# Preamp_schematic.net
KiCad netlist of a schematic drawn in Altium Designer
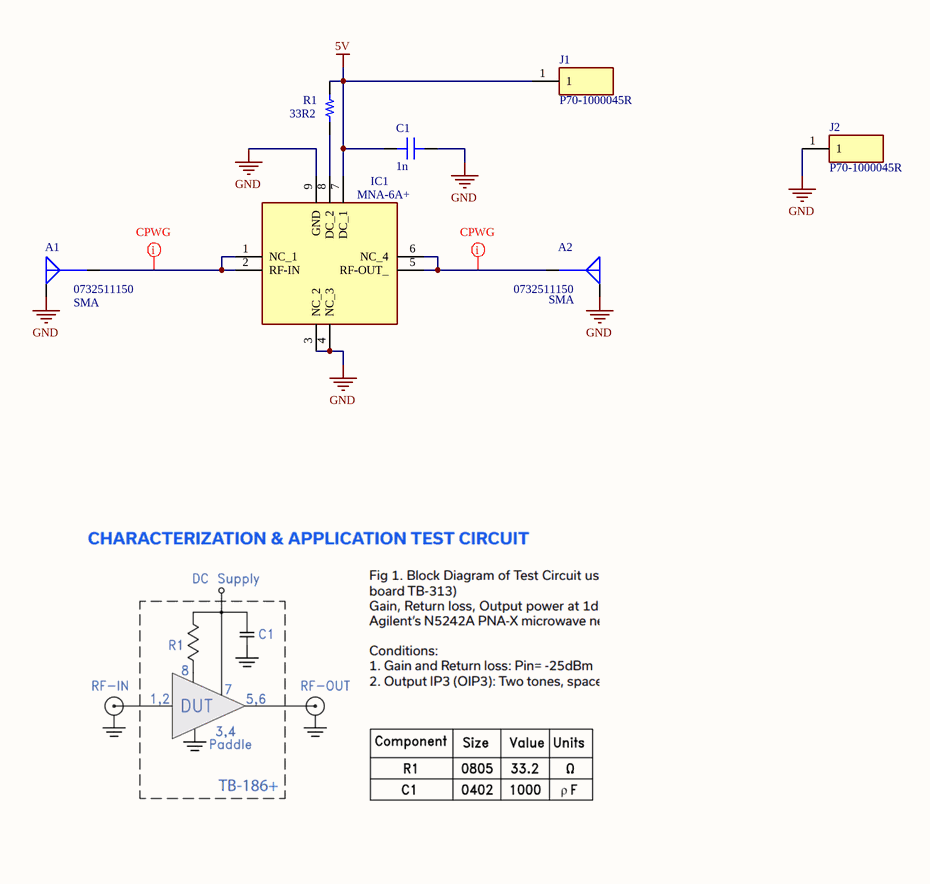
[diagram p0: Preamp_schematic.SchDoc]

(export (version "E")
  (design (tool "Eeschema 10.0.6"))
  (components
    (comp (ref "A1")
      (value "0732511150")
      (footprint "MOLEX SD-73251-115")
      (description "CONN SMA RCPT STR 50OHM EDGE MNT")
      (fields (field (name "CONNECTOR STYLE") "SMA") (field (name "MANUFACTURER") "Molex"))
      (libsource (lib "Celestial Altium Library - altium_library") (part "Basic Antenna"))
    )
    (comp (ref "A2")
      (value "0732511150")
      (footprint "MOLEX SD-73251-115")
      (description "CONN SMA RCPT STR 50OHM EDGE MNT")
      (fields (field (name "CONNECTOR STYLE") "SMA") (field (name "MANUFACTURER") "Molex"))
      (libsource (lib "Celestial Altium Library - altium_library") (part "Basic Antenna"))
    )
    (comp (ref "C1")
      (value "1n")
      (footprint "CAP 0603_1608 RF")
      (description "CAP CER 1000PF 50V 0603")
      (fields (field (name "PART NUMBER") "UMK107SD102JA-T") (field (name "MANUFACTURER") "Taiyo Yuden"))
      (libsource (lib "Celestial Altium Library - altium_library") (part "Capacitor"))
    )
    (comp (ref "IC1")
      (value "MNA-6A+")
      (footprint "SamacSys:MNA6A")
      (description "Integrated Circuit")
      (fields (field (name "MOUSER PART NUMBER") "139-MNA-6A"))
      (libsource (lib "*") (part "MNA-6A+"))
    )
    (comp (ref "J1")
      (value "P70-1000045R")
      (footprint "SamacSys:P701000045R")
      (description "Connector")
      (fields (field (name "MOUSER PART NUMBER") "855-P70-1000045R"))
      (libsource (lib "*") (part "P70-1000045R"))
    )
    (comp (ref "J2")
      (value "P70-1000045R")
      (footprint "SamacSys:P701000045R")
      (description "Connector")
      (fields (field (name "MOUSER PART NUMBER") "855-P70-1000045R"))
      (libsource (lib "*") (part "P70-1000045R"))
    )
    (comp (ref "R1")
      (value "33R2")
      (footprint "RES 0805_2012")
      (description "RES SMD 33.2 OHM 1% 1/2W 0805")
      (fields (field (name "PART NUMBER") "RCS080533R2FKEA") (field (name "MANUFACTURER") "Vishay Dale"))
      (libsource (lib "Celestial Altium Library - altium_library") (part "Resistor"))
    )
  )
  (nets
    (net (code "1") (name "5V") (class "Default")
      (node (ref "C1") (pin "1") (pinfunction "1_1") (pintype "passive"))
      (node (ref "IC1") (pin "7") (pinfunction "DC_1_7") (pintype "passive"))
      (node (ref "J1") (pin "1") (pinfunction "1_1") (pintype "passive"))
      (node (ref "R1") (pin "2") (pinfunction "2_2") (pintype "passive"))
    )
    (net (code "2") (name "GND") (class "Default")
      (node (ref "A1") (pin "G") (pinfunction "G_G") (pintype "passive"))
      (node (ref "A2") (pin "G") (pinfunction "G_G") (pintype "passive"))
      (node (ref "C1") (pin "2") (pinfunction "2_2") (pintype "passive"))
      (node (ref "IC1") (pin "3") (pinfunction "NC_2_3") (pintype "passive"))
      (node (ref "IC1") (pin "4") (pinfunction "NC_3_4") (pintype "passive"))
      (node (ref "IC1") (pin "9") (pinfunction "GND_9") (pintype "passive"))
      (node (ref "J2") (pin "1") (pinfunction "1_1") (pintype "passive"))
    )
    (net (code "3") (name "Net-(IC1-DC_2)") (class "Default")
      (node (ref "IC1") (pin "8") (pinfunction "DC_2_8") (pintype "passive"))
      (node (ref "R1") (pin "1") (pinfunction "1_1") (pintype "passive"))
    )
    (net (code "4") (name "Net-(IC1-NC_1)") (class "Default")
      (node (ref "A1") (pin "S") (pinfunction "S_S") (pintype "passive"))
      (node (ref "IC1") (pin "1") (pinfunction "NC_1_1") (pintype "passive"))
      (node (ref "IC1") (pin "2") (pinfunction "RF-IN_2") (pintype "passive"))
    )
    (net (code "5") (name "Net-(IC1-NC_4)") (class "Default")
      (node (ref "A2") (pin "S") (pinfunction "S_S") (pintype "passive"))
      (node (ref "IC1") (pin "5") (pinfunction "RF-OUT__5") (pintype "passive"))
      (node (ref "IC1") (pin "6") (pinfunction "NC_4_6") (pintype "passive"))
    )
  )
)
